# pwm_driver.net
KiCad netlist of a schematic drawn in EAGLE
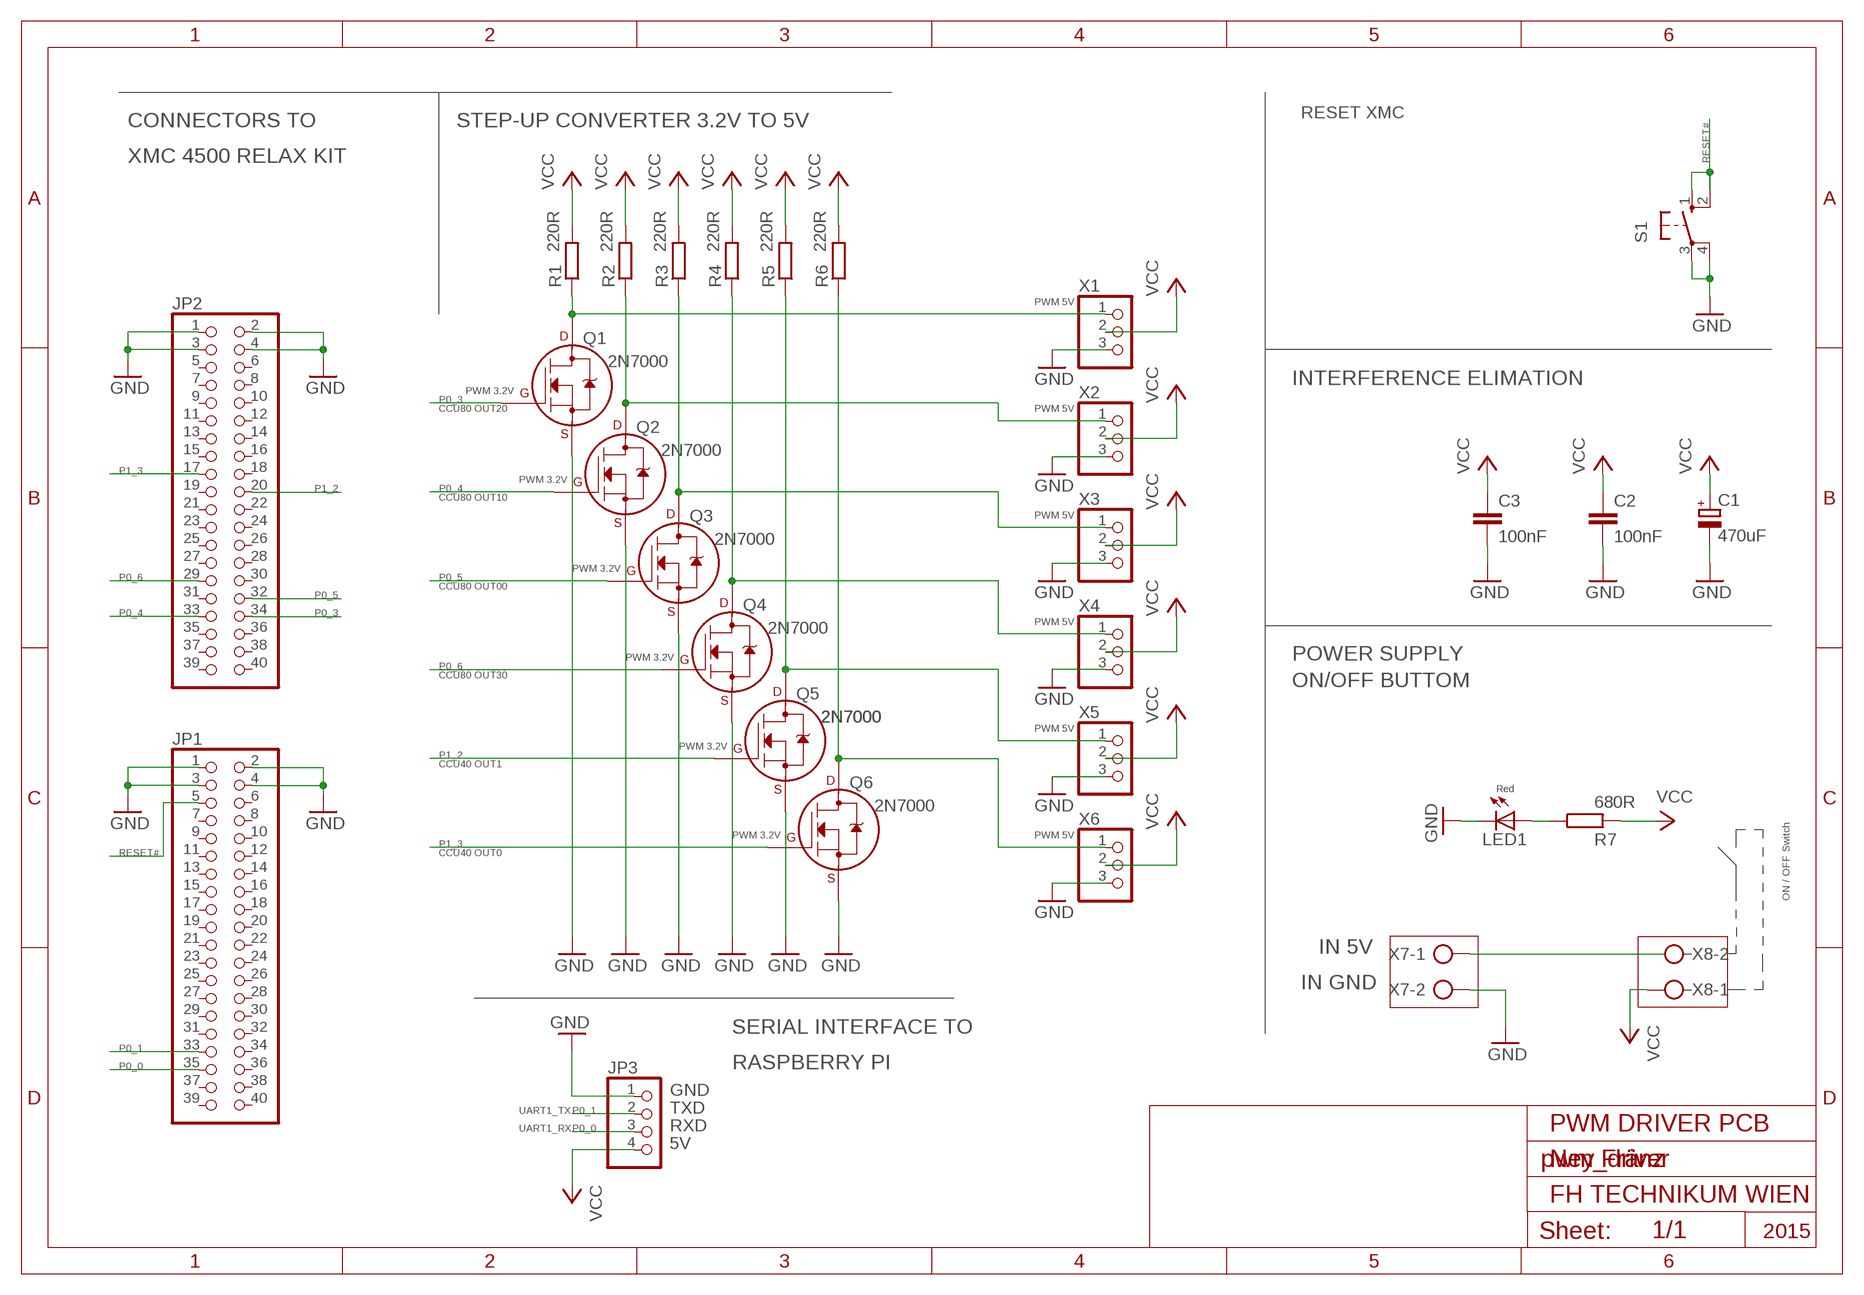
[diagram p0: schematic, sheet 1]

(export (version "E")
  (design (tool "Eeschema 10.0.6"))
  (components
    (comp (ref "C1")
      (value "470uF")
      (footprint "eagle-import:E3,5-10")
      (libsource (lib "eagle-import") (part "CPOL-EUE3.5-10"))
    )
    (comp (ref "C2")
      (value "100nF")
      (footprint "eagle-import:C025-024X044")
      (libsource (lib "eagle-import") (part "C-EU025-024X044"))
    )
    (comp (ref "C3")
      (value "100nF")
      (footprint "eagle-import:C025-024X044")
      (libsource (lib "eagle-import") (part "C-EU025-024X044"))
    )
    (comp (ref "JP1")
      (value "PINHD-2X20")
      (footprint "eagle-import:2X20")
      (libsource (lib "eagle-import") (part "PINHD-2X20"))
    )
    (comp (ref "JP2")
      (value "PINHD-2X20")
      (footprint "eagle-import:2X20")
      (libsource (lib "eagle-import") (part "PINHD-2X20"))
    )
    (comp (ref "JP3")
      (value "PINHD-1X4")
      (footprint "eagle-import:1X04")
      (libsource (lib "eagle-import") (part "PINHD-1X4"))
    )
    (comp (ref "LED1")
      (value "LED3MM")
      (footprint "eagle-import:LED3MM")
      (libsource (lib "eagle-import") (part "LED3MM"))
    )
    (comp (ref "Q1")
      (value "2N7000_TO92")
      (footprint "eagle-import:TO-92")
      (libsource (lib "eagle-import") (part "2N700_TO920"))
    )
    (comp (ref "Q2")
      (value "2N7000_TO92")
      (footprint "eagle-import:TO-92")
      (libsource (lib "eagle-import") (part "2N700_TO920"))
    )
    (comp (ref "Q3")
      (value "2N7000_TO92")
      (footprint "eagle-import:TO-92")
      (libsource (lib "eagle-import") (part "2N700_TO920"))
    )
    (comp (ref "Q4")
      (value "2N7000_TO92")
      (footprint "eagle-import:TO-92")
      (libsource (lib "eagle-import") (part "2N700_TO920"))
    )
    (comp (ref "Q5")
      (value "2N7000_TO92")
      (footprint "eagle-import:TO-92")
      (libsource (lib "eagle-import") (part "2N700_TO920"))
    )
    (comp (ref "Q6")
      (value "2N7000_TO92")
      (footprint "eagle-import:TO-92")
      (libsource (lib "eagle-import") (part "2N700_TO920"))
    )
    (comp (ref "R1")
      (value "220R")
      (footprint "eagle-import:0207_10")
      (libsource (lib "eagle-import") (part "R-EU_0207/10"))
    )
    (comp (ref "R2")
      (value "220R")
      (footprint "eagle-import:0207_10")
      (libsource (lib "eagle-import") (part "R-EU_0207/10"))
    )
    (comp (ref "R3")
      (value "220R")
      (footprint "eagle-import:0207_10")
      (libsource (lib "eagle-import") (part "R-EU_0207/10"))
    )
    (comp (ref "R4")
      (value "220R")
      (footprint "eagle-import:0207_10")
      (libsource (lib "eagle-import") (part "R-EU_0207/10"))
    )
    (comp (ref "R5")
      (value "220R")
      (footprint "eagle-import:0207_10")
      (libsource (lib "eagle-import") (part "R-EU_0207/10"))
    )
    (comp (ref "R6")
      (value "220R")
      (footprint "eagle-import:0207_10")
      (libsource (lib "eagle-import") (part "R-EU_0207/10"))
    )
    (comp (ref "R7")
      (value "680R")
      (footprint "eagle-import:0207_10")
      (libsource (lib "eagle-import") (part "R-EU_0207/10"))
    )
    (comp (ref "S1")
      (value "10-XX")
      (footprint "eagle-import:B3F-10XX")
      (fields (field (name "MPN") "B3F-1000"))
      (libsource (lib "eagle-import") (part "10-XX"))
    )
    (comp (ref "X1")
      (value "PINHD-1X3")
      (footprint "eagle-import:1X03")
      (libsource (lib "eagle-import") (part "PINHD-1X3"))
    )
    (comp (ref "X2")
      (value "PINHD-1X3")
      (footprint "eagle-import:1X03")
      (libsource (lib "eagle-import") (part "PINHD-1X3"))
    )
    (comp (ref "X3")
      (value "PINHD-1X3")
      (footprint "eagle-import:1X03")
      (libsource (lib "eagle-import") (part "PINHD-1X3"))
    )
    (comp (ref "X4")
      (value "PINHD-1X3")
      (footprint "eagle-import:1X03")
      (libsource (lib "eagle-import") (part "PINHD-1X3"))
    )
    (comp (ref "X5")
      (value "PINHD-1X3")
      (footprint "eagle-import:1X03")
      (libsource (lib "eagle-import") (part "PINHD-1X3"))
    )
    (comp (ref "X6")
      (value "PINHD-1X3")
      (footprint "eagle-import:1X03")
      (libsource (lib "eagle-import") (part "PINHD-1X3"))
    )
    (comp (ref "X7")
      (value "AK500/2")
      (footprint "eagle-import:AK500_2")
      (libsource (lib "eagle-import") (part "AK500/2"))
    )
    (comp (ref "X8")
      (value "AK500/2")
      (footprint "eagle-import:AK500_2")
      (libsource (lib "eagle-import") (part "AK500/2"))
    )
  )
  (nets
    (net (code "1") (name "/P0_0") (class "Default")
      (node (ref "JP1") (pin "35") (pinfunction "35_35") (pintype "passive"))
      (node (ref "JP3") (pin "3") (pinfunction "3_3") (pintype "passive"))
    )
    (net (code "2") (name "/P0_1") (class "Default")
      (node (ref "JP1") (pin "33") (pinfunction "33_33") (pintype "passive"))
      (node (ref "JP3") (pin "2") (pinfunction "2_2") (pintype "passive"))
    )
    (net (code "3") (name "/P0_3") (class "Default")
      (node (ref "JP2") (pin "34") (pinfunction "34_34") (pintype "passive"))
      (node (ref "Q1") (pin "2") (pinfunction "G_2") (pintype "tri_state"))
    )
    (net (code "4") (name "/P0_4") (class "Default")
      (node (ref "JP2") (pin "33") (pinfunction "33_33") (pintype "passive"))
      (node (ref "Q2") (pin "2") (pinfunction "G_2") (pintype "tri_state"))
    )
    (net (code "5") (name "/P0_5") (class "Default")
      (node (ref "JP2") (pin "32") (pinfunction "32_32") (pintype "passive"))
      (node (ref "Q3") (pin "2") (pinfunction "G_2") (pintype "tri_state"))
    )
    (net (code "6") (name "/P0_6") (class "Default")
      (node (ref "JP2") (pin "29") (pinfunction "29_29") (pintype "passive"))
      (node (ref "Q4") (pin "2") (pinfunction "G_2") (pintype "tri_state"))
    )
    (net (code "7") (name "/P1_2") (class "Default")
      (node (ref "JP2") (pin "20") (pinfunction "20_20") (pintype "passive"))
      (node (ref "Q5") (pin "2") (pinfunction "G_2") (pintype "tri_state"))
    )
    (net (code "8") (name "/P1_3") (class "Default")
      (node (ref "JP2") (pin "17") (pinfunction "17_17") (pintype "passive"))
      (node (ref "Q6") (pin "2") (pinfunction "G_2") (pintype "tri_state"))
    )
    (net (code "9") (name "/RESET") (class "Default")
      (node (ref "JP1") (pin "5") (pinfunction "5_5") (pintype "passive"))
      (node (ref "S1") (pin "1") (pinfunction "S_1") (pintype "passive"))
      (node (ref "S1") (pin "2") (pinfunction "S1_2") (pintype "passive"))
    )
    (net (code "10") (name "GND") (class "Default")
      (node (ref "C1") (pin "-") (pinfunction "-_-") (pintype "passive"))
      (node (ref "C2") (pin "2") (pinfunction "2_2") (pintype "passive"))
      (node (ref "C3") (pin "2") (pinfunction "2_2") (pintype "passive"))
      (node (ref "JP1") (pin "1") (pinfunction "1_1") (pintype "passive"))
      (node (ref "JP1") (pin "2") (pinfunction "2_2") (pintype "passive"))
      (node (ref "JP1") (pin "3") (pinfunction "3_3") (pintype "passive"))
      (node (ref "JP1") (pin "4") (pinfunction "4_4") (pintype "passive"))
      (node (ref "JP2") (pin "1") (pinfunction "1_1") (pintype "passive"))
      (node (ref "JP2") (pin "2") (pinfunction "2_2") (pintype "passive"))
      (node (ref "JP2") (pin "3") (pinfunction "3_3") (pintype "passive"))
      (node (ref "JP2") (pin "4") (pinfunction "4_4") (pintype "passive"))
      (node (ref "JP3") (pin "1") (pinfunction "1_1") (pintype "passive"))
      (node (ref "LED1") (pin "K") (pinfunction "C_K") (pintype "passive"))
      (node (ref "Q1") (pin "1") (pinfunction "S_1") (pintype "bidirectional"))
      (node (ref "Q2") (pin "1") (pinfunction "S_1") (pintype "bidirectional"))
      (node (ref "Q3") (pin "1") (pinfunction "S_1") (pintype "bidirectional"))
      (node (ref "Q4") (pin "1") (pinfunction "S_1") (pintype "bidirectional"))
      (node (ref "Q5") (pin "1") (pinfunction "S_1") (pintype "bidirectional"))
      (node (ref "Q6") (pin "1") (pinfunction "S_1") (pintype "bidirectional"))
      (node (ref "S1") (pin "3") (pinfunction "P_3") (pintype "passive"))
      (node (ref "S1") (pin "4") (pinfunction "P1_4") (pintype "passive"))
      (node (ref "X1") (pin "3") (pinfunction "3_3") (pintype "passive"))
      (node (ref "X2") (pin "3") (pinfunction "3_3") (pintype "passive"))
      (node (ref "X3") (pin "3") (pinfunction "3_3") (pintype "passive"))
      (node (ref "X4") (pin "3") (pinfunction "3_3") (pintype "passive"))
      (node (ref "X5") (pin "3") (pinfunction "3_3") (pintype "passive"))
      (node (ref "X6") (pin "3") (pinfunction "3_3") (pintype "passive"))
      (node (ref "X7") (pin "2") (pinfunction "KL_2") (pintype "passive"))
    )
    (net (code "11") (name "Net-(LED1-PadA)") (class "Default")
      (node (ref "LED1") (pin "A") (pinfunction "A_A") (pintype "passive"))
      (node (ref "R7") (pin "1") (pinfunction "1_1") (pintype "passive"))
    )
    (net (code "12") (name "Net-(Q1-D)") (class "Default")
      (node (ref "Q1") (pin "3") (pinfunction "D_3") (pintype "bidirectional"))
      (node (ref "R1") (pin "1") (pinfunction "1_1") (pintype "passive"))
      (node (ref "X1") (pin "1") (pinfunction "1_1") (pintype "passive"))
    )
    (net (code "13") (name "Net-(Q2-D)") (class "Default")
      (node (ref "Q2") (pin "3") (pinfunction "D_3") (pintype "bidirectional"))
      (node (ref "R2") (pin "1") (pinfunction "1_1") (pintype "passive"))
      (node (ref "X2") (pin "1") (pinfunction "1_1") (pintype "passive"))
    )
    (net (code "14") (name "Net-(Q3-D)") (class "Default")
      (node (ref "Q3") (pin "3") (pinfunction "D_3") (pintype "bidirectional"))
      (node (ref "R3") (pin "1") (pinfunction "1_1") (pintype "passive"))
      (node (ref "X3") (pin "1") (pinfunction "1_1") (pintype "passive"))
    )
    (net (code "15") (name "Net-(Q4-D)") (class "Default")
      (node (ref "Q4") (pin "3") (pinfunction "D_3") (pintype "bidirectional"))
      (node (ref "R4") (pin "1") (pinfunction "1_1") (pintype "passive"))
      (node (ref "X4") (pin "1") (pinfunction "1_1") (pintype "passive"))
    )
    (net (code "16") (name "Net-(Q5-D)") (class "Default")
      (node (ref "Q5") (pin "3") (pinfunction "D_3") (pintype "bidirectional"))
      (node (ref "R5") (pin "1") (pinfunction "1_1") (pintype "passive"))
      (node (ref "X5") (pin "1") (pinfunction "1_1") (pintype "passive"))
    )
    (net (code "17") (name "Net-(Q6-D)") (class "Default")
      (node (ref "Q6") (pin "3") (pinfunction "D_3") (pintype "bidirectional"))
      (node (ref "R6") (pin "1") (pinfunction "1_1") (pintype "passive"))
      (node (ref "X6") (pin "1") (pinfunction "1_1") (pintype "passive"))
    )
    (net (code "18") (name "Net-(X7A-KL)") (class "Default")
      (node (ref "X7") (pin "1") (pinfunction "KL_1") (pintype "passive"))
      (node (ref "X8") (pin "2") (pinfunction "KL_2") (pintype "passive"))
    )
    (net (code "19") (name "VCC") (class "Default")
      (node (ref "C1") (pin "+") (pinfunction "+_+") (pintype "passive"))
      (node (ref "C2") (pin "1") (pinfunction "1_1") (pintype "passive"))
      (node (ref "C3") (pin "1") (pinfunction "1_1") (pintype "passive"))
      (node (ref "JP3") (pin "4") (pinfunction "4_4") (pintype "passive"))
      (node (ref "R1") (pin "2") (pinfunction "2_2") (pintype "passive"))
      (node (ref "R2") (pin "2") (pinfunction "2_2") (pintype "passive"))
      (node (ref "R3") (pin "2") (pinfunction "2_2") (pintype "passive"))
      (node (ref "R4") (pin "2") (pinfunction "2_2") (pintype "passive"))
      (node (ref "R5") (pin "2") (pinfunction "2_2") (pintype "passive"))
      (node (ref "R6") (pin "2") (pinfunction "2_2") (pintype "passive"))
      (node (ref "R7") (pin "2") (pinfunction "2_2") (pintype "passive"))
      (node (ref "X1") (pin "2") (pinfunction "2_2") (pintype "passive"))
      (node (ref "X2") (pin "2") (pinfunction "2_2") (pintype "passive"))
      (node (ref "X3") (pin "2") (pinfunction "2_2") (pintype "passive"))
      (node (ref "X4") (pin "2") (pinfunction "2_2") (pintype "passive"))
      (node (ref "X5") (pin "2") (pinfunction "2_2") (pintype "passive"))
      (node (ref "X6") (pin "2") (pinfunction "2_2") (pintype "passive"))
      (node (ref "X8") (pin "1") (pinfunction "KL_1") (pintype "passive"))
    )
    (net (code "20") (name "unconnected-(JP1-Pad6)") (class "Default")
      (node (ref "JP1") (pin "6") (pinfunction "6_6") (pintype "passive"))
    )
    (net (code "21") (name "unconnected-(JP1-Pad7)") (class "Default")
      (node (ref "JP1") (pin "7") (pinfunction "7_7") (pintype "passive"))
    )
    (net (code "22") (name "unconnected-(JP1-Pad8)") (class "Default")
      (node (ref "JP1") (pin "8") (pinfunction "8_8") (pintype "passive"))
    )
    (net (code "23") (name "unconnected-(JP1-Pad9)") (class "Default")
      (node (ref "JP1") (pin "9") (pinfunction "9_9") (pintype "passive"))
    )
    (net (code "24") (name "unconnected-(JP1-Pad10)") (class "Default")
      (node (ref "JP1") (pin "10") (pinfunction "10_10") (pintype "passive"))
    )
    (net (code "25") (name "unconnected-(JP1-Pad11)") (class "Default")
      (node (ref "JP1") (pin "11") (pinfunction "11_11") (pintype "passive"))
    )
    (net (code "26") (name "unconnected-(JP1-Pad12)") (class "Default")
      (node (ref "JP1") (pin "12") (pinfunction "12_12") (pintype "passive"))
    )
    (net (code "27") (name "unconnected-(JP1-Pad13)") (class "Default")
      (node (ref "JP1") (pin "13") (pinfunction "13_13") (pintype "passive"))
    )
    (net (code "28") (name "unconnected-(JP1-Pad14)") (class "Default")
      (node (ref "JP1") (pin "14") (pinfunction "14_14") (pintype "passive"))
    )
    (net (code "29") (name "unconnected-(JP1-Pad15)") (class "Default")
      (node (ref "JP1") (pin "15") (pinfunction "15_15") (pintype "passive"))
    )
    (net (code "30") (name "unconnected-(JP1-Pad16)") (class "Default")
      (node (ref "JP1") (pin "16") (pinfunction "16_16") (pintype "passive"))
    )
    (net (code "31") (name "unconnected-(JP1-Pad17)") (class "Default")
      (node (ref "JP1") (pin "17") (pinfunction "17_17") (pintype "passive"))
    )
    (net (code "32") (name "unconnected-(JP1-Pad18)") (class "Default")
      (node (ref "JP1") (pin "18") (pinfunction "18_18") (pintype "passive"))
    )
    (net (code "33") (name "unconnected-(JP1-Pad19)") (class "Default")
      (node (ref "JP1") (pin "19") (pinfunction "19_19") (pintype "passive"))
    )
    (net (code "34") (name "unconnected-(JP1-Pad20)") (class "Default")
      (node (ref "JP1") (pin "20") (pinfunction "20_20") (pintype "passive"))
    )
    (net (code "35") (name "unconnected-(JP1-Pad21)") (class "Default")
      (node (ref "JP1") (pin "21") (pinfunction "21_21") (pintype "passive"))
    )
    (net (code "36") (name "unconnected-(JP1-Pad22)") (class "Default")
      (node (ref "JP1") (pin "22") (pinfunction "22_22") (pintype "passive"))
    )
    (net (code "37") (name "unconnected-(JP1-Pad23)") (class "Default")
      (node (ref "JP1") (pin "23") (pinfunction "23_23") (pintype "passive"))
    )
    (net (code "38") (name "unconnected-(JP1-Pad24)") (class "Default")
      (node (ref "JP1") (pin "24") (pinfunction "24_24") (pintype "passive"))
    )
    (net (code "39") (name "unconnected-(JP1-Pad25)") (class "Default")
      (node (ref "JP1") (pin "25") (pinfunction "25_25") (pintype "passive"))
    )
    (net (code "40") (name "unconnected-(JP1-Pad26)") (class "Default")
      (node (ref "JP1") (pin "26") (pinfunction "26_26") (pintype "passive"))
    )
    (net (code "41") (name "unconnected-(JP1-Pad27)") (class "Default")
      (node (ref "JP1") (pin "27") (pinfunction "27_27") (pintype "passive"))
    )
    (net (code "42") (name "unconnected-(JP1-Pad28)") (class "Default")
      (node (ref "JP1") (pin "28") (pinfunction "28_28") (pintype "passive"))
    )
    (net (code "43") (name "unconnected-(JP1-Pad29)") (class "Default")
      (node (ref "JP1") (pin "29") (pinfunction "29_29") (pintype "passive"))
    )
    (net (code "44") (name "unconnected-(JP1-Pad30)") (class "Default")
      (node (ref "JP1") (pin "30") (pinfunction "30_30") (pintype "passive"))
    )
    (net (code "45") (name "unconnected-(JP1-Pad31)") (class "Default")
      (node (ref "JP1") (pin "31") (pinfunction "31_31") (pintype "passive"))
    )
    (net (code "46") (name "unconnected-(JP1-Pad32)") (class "Default")
      (node (ref "JP1") (pin "32") (pinfunction "32_32") (pintype "passive"))
    )
    (net (code "47") (name "unconnected-(JP1-Pad34)") (class "Default")
      (node (ref "JP1") (pin "34") (pinfunction "34_34") (pintype "passive"))
    )
    (net (code "48") (name "unconnected-(JP1-Pad36)") (class "Default")
      (node (ref "JP1") (pin "36") (pinfunction "36_36") (pintype "passive"))
    )
    (net (code "49") (name "unconnected-(JP1-Pad37)") (class "Default")
      (node (ref "JP1") (pin "37") (pinfunction "37_37") (pintype "passive"))
    )
    (net (code "50") (name "unconnected-(JP1-Pad38)") (class "Default")
      (node (ref "JP1") (pin "38") (pinfunction "38_38") (pintype "passive"))
    )
    (net (code "51") (name "unconnected-(JP1-Pad39)") (class "Default")
      (node (ref "JP1") (pin "39") (pinfunction "39_39") (pintype "passive"))
    )
    (net (code "52") (name "unconnected-(JP1-Pad40)") (class "Default")
      (node (ref "JP1") (pin "40") (pinfunction "40_40") (pintype "passive"))
    )
    (net (code "53") (name "unconnected-(JP2-Pad5)") (class "Default")
      (node (ref "JP2") (pin "5") (pinfunction "5_5") (pintype "passive"))
    )
    (net (code "54") (name "unconnected-(JP2-Pad6)") (class "Default")
      (node (ref "JP2") (pin "6") (pinfunction "6_6") (pintype "passive"))
    )
    (net (code "55") (name "unconnected-(JP2-Pad7)") (class "Default")
      (node (ref "JP2") (pin "7") (pinfunction "7_7") (pintype "passive"))
    )
    (net (code "56") (name "unconnected-(JP2-Pad8)") (class "Default")
      (node (ref "JP2") (pin "8") (pinfunction "8_8") (pintype "passive"))
    )
    (net (code "57") (name "unconnected-(JP2-Pad9)") (class "Default")
      (node (ref "JP2") (pin "9") (pinfunction "9_9") (pintype "passive"))
    )
    (net (code "58") (name "unconnected-(JP2-Pad10)") (class "Default")
      (node (ref "JP2") (pin "10") (pinfunction "10_10") (pintype "passive"))
    )
    (net (code "59") (name "unconnected-(JP2-Pad11)") (class "Default")
      (node (ref "JP2") (pin "11") (pinfunction "11_11") (pintype "passive"))
    )
    (net (code "60") (name "unconnected-(JP2-Pad12)") (class "Default")
      (node (ref "JP2") (pin "12") (pinfunction "12_12") (pintype "passive"))
    )
    (net (code "61") (name "unconnected-(JP2-Pad13)") (class "Default")
      (node (ref "JP2") (pin "13") (pinfunction "13_13") (pintype "passive"))
    )
    (net (code "62") (name "unconnected-(JP2-Pad14)") (class "Default")
      (node (ref "JP2") (pin "14") (pinfunction "14_14") (pintype "passive"))
    )
    (net (code "63") (name "unconnected-(JP2-Pad15)") (class "Default")
      (node (ref "JP2") (pin "15") (pinfunction "15_15") (pintype "passive"))
    )
    (net (code "64") (name "unconnected-(JP2-Pad16)") (class "Default")
      (node (ref "JP2") (pin "16") (pinfunction "16_16") (pintype "passive"))
    )
    (net (code "65") (name "unconnected-(JP2-Pad18)") (class "Default")
      (node (ref "JP2") (pin "18") (pinfunction "18_18") (pintype "passive"))
    )
    (net (code "66") (name "unconnected-(JP2-Pad19)") (class "Default")
      (node (ref "JP2") (pin "19") (pinfunction "19_19") (pintype "passive"))
    )
    (net (code "67") (name "unconnected-(JP2-Pad21)") (class "Default")
      (node (ref "JP2") (pin "21") (pinfunction "21_21") (pintype "passive"))
    )
    (net (code "68") (name "unconnected-(JP2-Pad22)") (class "Default")
      (node (ref "JP2") (pin "22") (pinfunction "22_22") (pintype "passive"))
    )
    (net (code "69") (name "unconnected-(JP2-Pad23)") (class "Default")
      (node (ref "JP2") (pin "23") (pinfunction "23_23") (pintype "passive"))
    )
    (net (code "70") (name "unconnected-(JP2-Pad24)") (class "Default")
      (node (ref "JP2") (pin "24") (pinfunction "24_24") (pintype "passive"))
    )
    (net (code "71") (name "unconnected-(JP2-Pad25)") (class "Default")
      (node (ref "JP2") (pin "25") (pinfunction "25_25") (pintype "passive"))
    )
    (net (code "72") (name "unconnected-(JP2-Pad26)") (class "Default")
      (node (ref "JP2") (pin "26") (pinfunction "26_26") (pintype "passive"))
    )
    (net (code "73") (name "unconnected-(JP2-Pad27)") (class "Default")
      (node (ref "JP2") (pin "27") (pinfunction "27_27") (pintype "passive"))
    )
    (net (code "74") (name "unconnected-(JP2-Pad28)") (class "Default")
      (node (ref "JP2") (pin "28") (pinfunction "28_28") (pintype "passive"))
    )
    (net (code "75") (name "unconnected-(JP2-Pad30)") (class "Default")
      (node (ref "JP2") (pin "30") (pinfunction "30_30") (pintype "passive"))
    )
    (net (code "76") (name "unconnected-(JP2-Pad31)") (class "Default")
      (node (ref "JP2") (pin "31") (pinfunction "31_31") (pintype "passive"))
    )
    (net (code "77") (name "unconnected-(JP2-Pad35)") (class "Default")
      (node (ref "JP2") (pin "35") (pinfunction "35_35") (pintype "passive"))
    )
    (net (code "78") (name "unconnected-(JP2-Pad36)") (class "Default")
      (node (ref "JP2") (pin "36") (pinfunction "36_36") (pintype "passive"))
    )
    (net (code "79") (name "unconnected-(JP2-Pad37)") (class "Default")
      (node (ref "JP2") (pin "37") (pinfunction "37_37") (pintype "passive"))
    )
    (net (code "80") (name "unconnected-(JP2-Pad38)") (class "Default")
      (node (ref "JP2") (pin "38") (pinfunction "38_38") (pintype "passive"))
    )
    (net (code "81") (name "unconnected-(JP2-Pad39)") (class "Default")
      (node (ref "JP2") (pin "39") (pinfunction "39_39") (pintype "passive"))
    )
    (net (code "82") (name "unconnected-(JP2-Pad40)") (class "Default")
      (node (ref "JP2") (pin "40") (pinfunction "40_40") (pintype "passive"))
    )
  )
)
